# as14120_ddr.net
KiCad netlist of a schematic drawn in Altium Designer
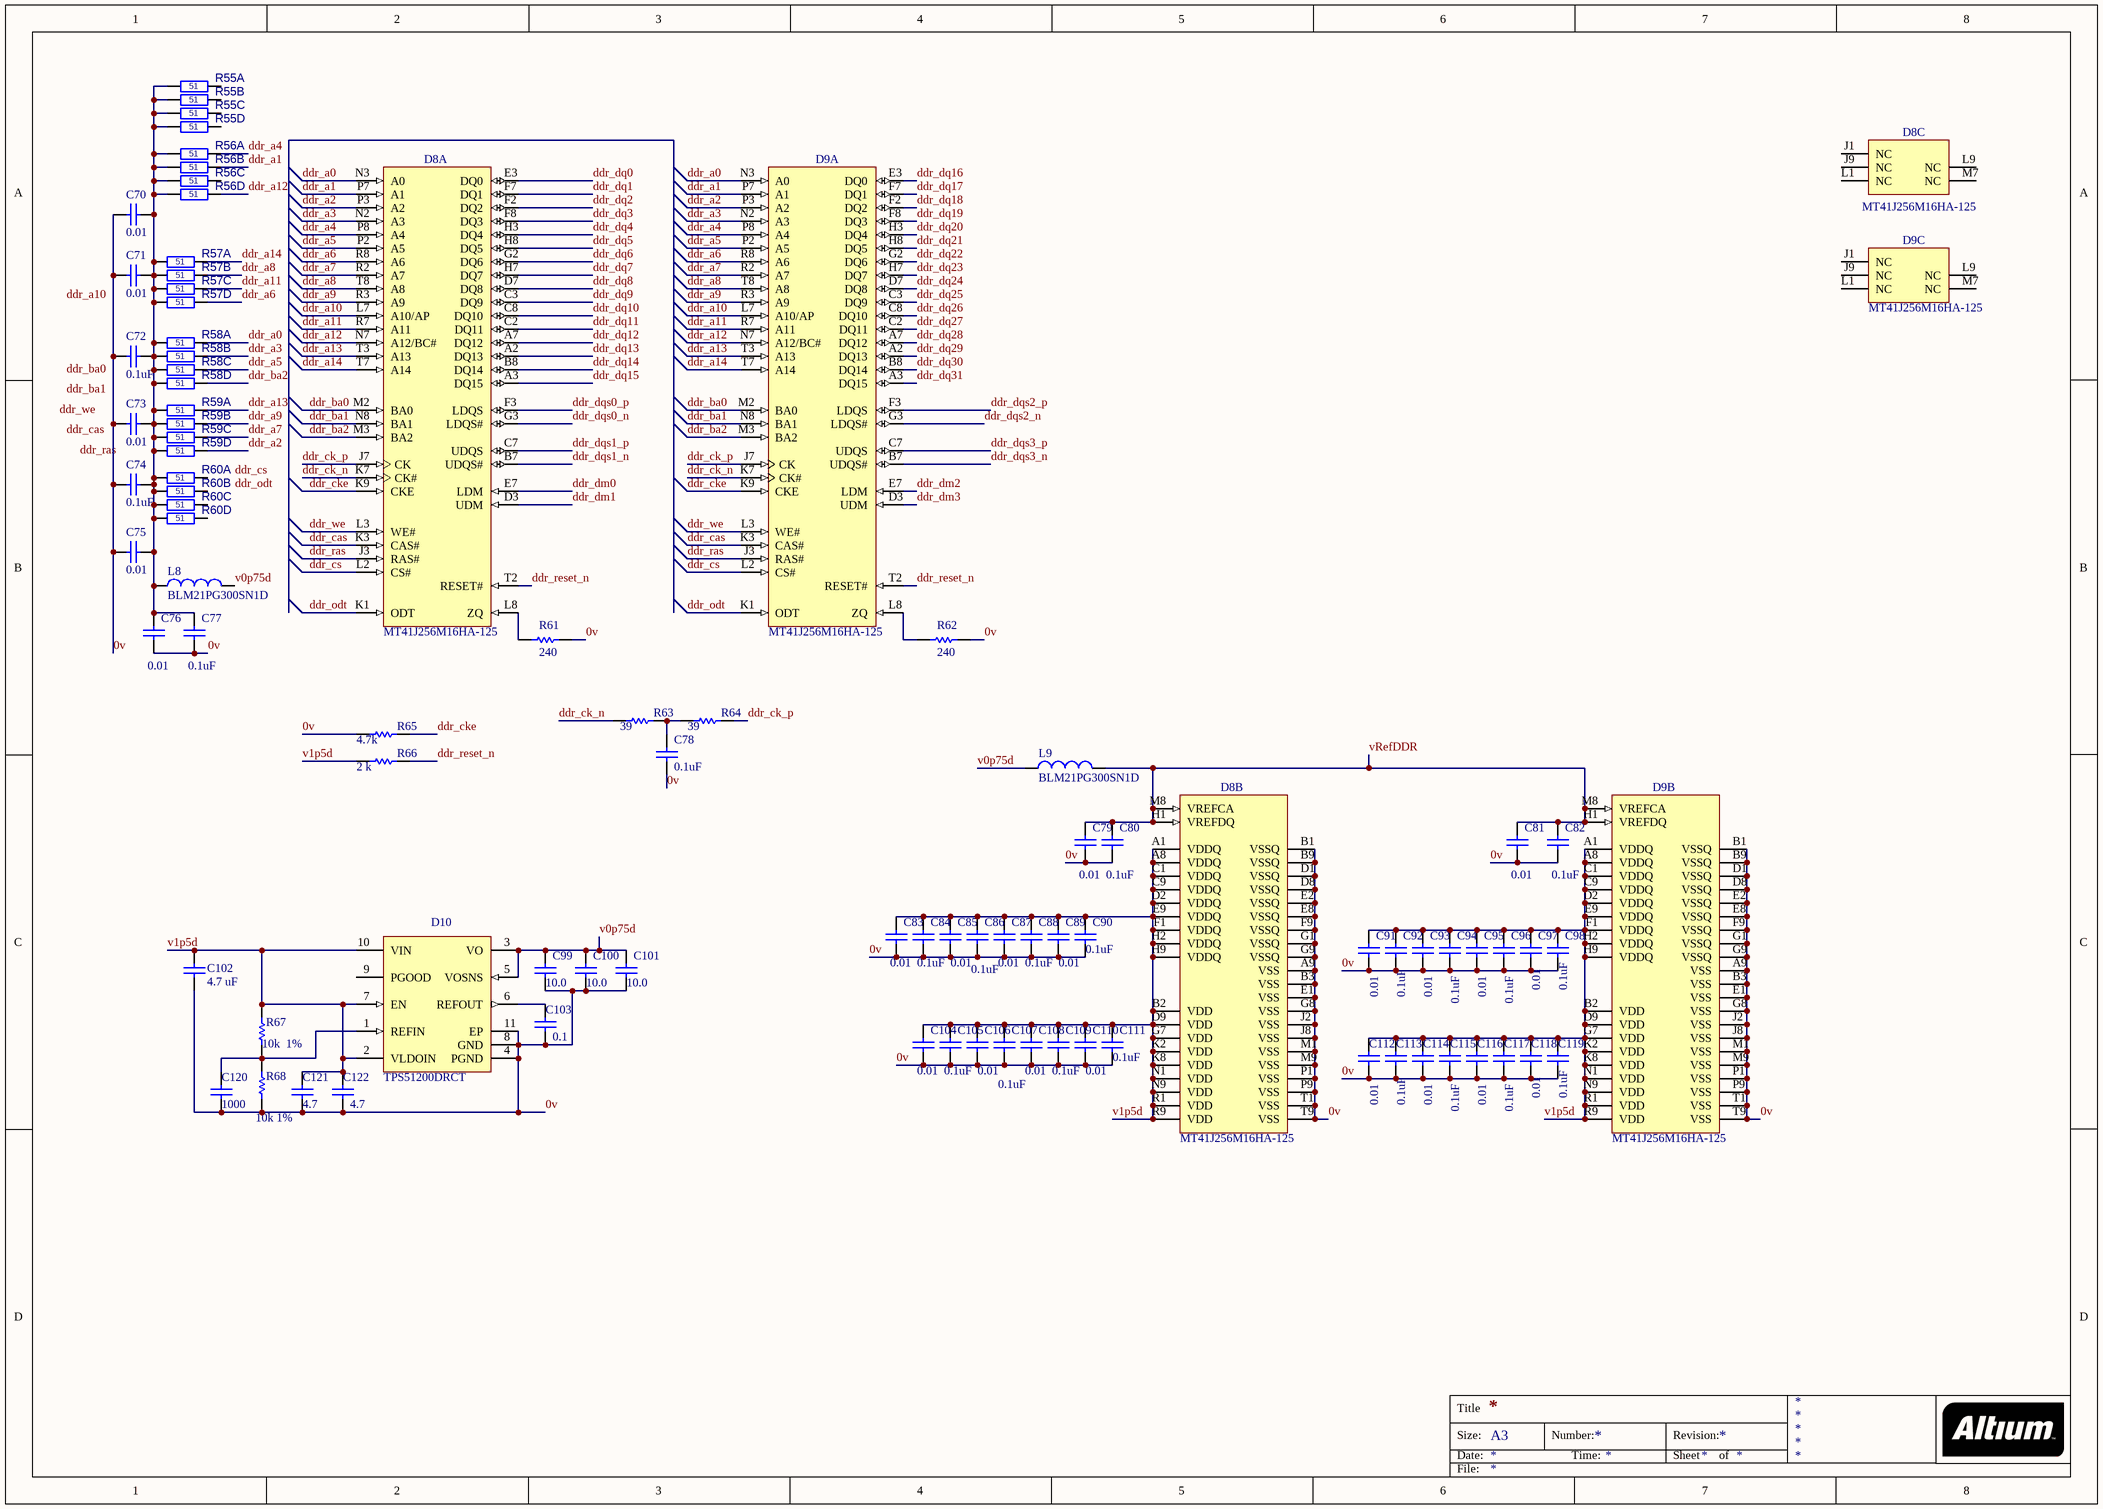
[diagram p0: as14120_ddr.SchDoc]

(export (version "E")
  (design (tool "Eeschema 10.0.6"))
  (components
    (comp (ref "C70")
      (value "0.01")
      (footprint "CAPC0402(1005)60_M")
      (description "CAP 1uF 10V ±20% 0402 (1005 Metric) Thickness 0.6mm SMD")
      (fields (field (name "TOLERANCE") "±20%") (field (name "Comment") "CAP 1uF 10V 0402(1005)"))
      (libsource (lib "as14120") (part "CAP_0402"))
    )
    (comp (ref "C71")
      (value "0.01")
      (footprint "CAPC0402(1005)60_M")
      (description "CAP 1uF 10V ±20% 0402 (1005 Metric) Thickness 0.6mm SMD")
      (fields (field (name "TOLERANCE") "±20%") (field (name "Comment") "CAP 1uF 10V 0402(1005)"))
      (libsource (lib "as14120") (part "CAP_0402"))
    )
    (comp (ref "C72")
      (value "0.1uF")
      (footprint "CAPC0402(1005)60_M")
      (description "CAP 1uF 10V ±20% 0402 (1005 Metric) Thickness 0.6mm SMD")
      (fields (field (name "TOLERANCE") "±20%") (field (name "Comment") "CAP 1uF 10V 0402(1005)"))
      (libsource (lib "as14120") (part "CAP_0402"))
    )
    (comp (ref "C73")
      (value "0.01")
      (footprint "CAPC0402(1005)60_M")
      (description "CAP 1uF 10V ±20% 0402 (1005 Metric) Thickness 0.6mm SMD")
      (fields (field (name "TOLERANCE") "±20%") (field (name "Comment") "CAP 1uF 10V 0402(1005)"))
      (libsource (lib "as14120") (part "CAP_0402"))
    )
    (comp (ref "C74")
      (value "0.1uF")
      (footprint "CAPC0402(1005)60_M")
      (description "CAP 1uF 10V ±20% 0402 (1005 Metric) Thickness 0.6mm SMD")
      (fields (field (name "TOLERANCE") "±20%") (field (name "Comment") "CAP 1uF 10V 0402(1005)"))
      (libsource (lib "as14120") (part "CAP_0402"))
    )
    (comp (ref "C75")
      (value "0.01")
      (footprint "CAPC0402(1005)60_M")
      (description "CAP 1uF 10V ±20% 0402 (1005 Metric) Thickness 0.6mm SMD")
      (fields (field (name "TOLERANCE") "±20%") (field (name "Comment") "CAP 1uF 10V 0402(1005)"))
      (libsource (lib "as14120") (part "CAP_0402"))
    )
    (comp (ref "C76")
      (value "0.01")
      (footprint "CAPC0402(1005)60_M")
      (description "CAP 1uF 10V ±20% 0402 (1005 Metric) Thickness 0.6mm SMD")
      (fields (field (name "TOLERANCE") "±20%") (field (name "Comment") "CAP 1uF 10V 0402(1005)"))
      (libsource (lib "as14120") (part "CAP_0402"))
    )
    (comp (ref "C77")
      (value "0.1uF")
      (footprint "CAPC0402(1005)60_M")
      (description "CAP 1uF 10V ±20% 0402 (1005 Metric) Thickness 0.6mm SMD")
      (fields (field (name "TOLERANCE") "±20%") (field (name "Comment") "CAP 1uF 10V 0402(1005)"))
      (libsource (lib "as14120") (part "CAP_0402"))
    )
    (comp (ref "C78")
      (value "0.1uF")
      (footprint "CAPC0402(1005)60_M")
      (description "CAP 1uF 10V ±20% 0402 (1005 Metric) Thickness 0.6mm SMD")
      (fields (field (name "TOLERANCE") "±20%") (field (name "Comment") "CAP 1uF 10V 0402(1005)"))
      (libsource (lib "as14120") (part "CAP_0402"))
    )
    (comp (ref "C79")
      (value "0.01")
      (footprint "CAPC0402(1005)60_M")
      (description "CAP 1uF 10V ±20% 0402 (1005 Metric) Thickness 0.6mm SMD")
      (fields (field (name "TOLERANCE") "±20%") (field (name "Comment") "CAP 1uF 10V 0402(1005)"))
      (libsource (lib "as14120") (part "CAP_0402"))
    )
    (comp (ref "C80")
      (value "0.1uF")
      (footprint "CAPC0402(1005)60_M")
      (description "CAP 1uF 10V ±20% 0402 (1005 Metric) Thickness 0.6mm SMD")
      (fields (field (name "TOLERANCE") "±20%") (field (name "Comment") "CAP 1uF 10V 0402(1005)"))
      (libsource (lib "as14120") (part "CAP_0402"))
    )
    (comp (ref "C81")
      (value "0.01")
      (footprint "CAPC0402(1005)60_M")
      (description "CAP 1uF 10V ±20% 0402 (1005 Metric) Thickness 0.6mm SMD")
      (fields (field (name "TOLERANCE") "±20%") (field (name "Comment") "CAP 1uF 10V 0402(1005)"))
      (libsource (lib "as14120") (part "CAP_0402"))
    )
    (comp (ref "C82")
      (value "0.1uF")
      (footprint "CAPC0402(1005)60_M")
      (description "CAP 1uF 10V ±20% 0402 (1005 Metric) Thickness 0.6mm SMD")
      (fields (field (name "TOLERANCE") "±20%") (field (name "Comment") "CAP 1uF 10V 0402(1005)"))
      (libsource (lib "as14120") (part "CAP_0402"))
    )
    (comp (ref "C83")
      (value "0.01")
      (footprint "CAPC0402(1005)60_M")
      (description "CAP 1uF 10V ±20% 0402 (1005 Metric) Thickness 0.6mm SMD")
      (fields (field (name "TOLERANCE") "±20%") (field (name "Comment") "CAP 1uF 10V 0402(1005)"))
      (libsource (lib "as14120") (part "CAP_0402"))
    )
    (comp (ref "C84")
      (value "0.1uF")
      (footprint "CAPC0402(1005)60_M")
      (description "CAP 1uF 10V ±20% 0402 (1005 Metric) Thickness 0.6mm SMD")
      (fields (field (name "TOLERANCE") "±20%") (field (name "Comment") "CAP 1uF 10V 0402(1005)"))
      (libsource (lib "as14120") (part "CAP_0402"))
    )
    (comp (ref "C85")
      (value "0.01")
      (footprint "CAPC0402(1005)60_M")
      (description "CAP 1uF 10V ±20% 0402 (1005 Metric) Thickness 0.6mm SMD")
      (fields (field (name "TOLERANCE") "±20%") (field (name "Comment") "CAP 1uF 10V 0402(1005)"))
      (libsource (lib "as14120") (part "CAP_0402"))
    )
    (comp (ref "C86")
      (value "0.1uF")
      (footprint "CAPC0402(1005)60_M")
      (description "CAP 1uF 10V ±20% 0402 (1005 Metric) Thickness 0.6mm SMD")
      (fields (field (name "TOLERANCE") "±20%") (field (name "Comment") "CAP 1uF 10V 0402(1005)"))
      (libsource (lib "as14120") (part "CAP_0402"))
    )
    (comp (ref "C87")
      (value "0.01")
      (footprint "CAPC0402(1005)60_M")
      (description "CAP 1uF 10V ±20% 0402 (1005 Metric) Thickness 0.6mm SMD")
      (fields (field (name "TOLERANCE") "±20%") (field (name "Comment") "CAP 1uF 10V 0402(1005)"))
      (libsource (lib "as14120") (part "CAP_0402"))
    )
    (comp (ref "C88")
      (value "0.1uF")
      (footprint "CAPC0402(1005)60_M")
      (description "CAP 1uF 10V ±20% 0402 (1005 Metric) Thickness 0.6mm SMD")
      (fields (field (name "TOLERANCE") "±20%") (field (name "Comment") "CAP 1uF 10V 0402(1005)"))
      (libsource (lib "as14120") (part "CAP_0402"))
    )
    (comp (ref "C89")
      (value "0.01")
      (footprint "CAPC0402(1005)60_M")
      (description "CAP 1uF 10V ±20% 0402 (1005 Metric) Thickness 0.6mm SMD")
      (fields (field (name "TOLERANCE") "±20%") (field (name "Comment") "CAP 1uF 10V 0402(1005)"))
      (libsource (lib "as14120") (part "CAP_0402"))
    )
    (comp (ref "C90")
      (value "0.1uF")
      (footprint "CAPC0402(1005)60_M")
      (description "CAP 1uF 10V ±20% 0402 (1005 Metric) Thickness 0.6mm SMD")
      (fields (field (name "TOLERANCE") "±20%") (field (name "Comment") "CAP 1uF 10V 0402(1005)"))
      (libsource (lib "as14120") (part "CAP_0402"))
    )
    (comp (ref "C91")
      (value "0.01")
      (footprint "CAPC0402(1005)60_M")
      (description "CAP 1uF 10V ±20% 0402 (1005 Metric) Thickness 0.6mm SMD")
      (fields (field (name "TOLERANCE") "±20%") (field (name "Comment") "CAP 1uF 10V 0402(1005)"))
      (libsource (lib "as14120") (part "CAP_0402"))
    )
    (comp (ref "C92")
      (value "0.1uF")
      (footprint "CAPC0402(1005)60_M")
      (description "CAP 1uF 10V ±20% 0402 (1005 Metric) Thickness 0.6mm SMD")
      (fields (field (name "TOLERANCE") "±20%") (field (name "Comment") "CAP 1uF 10V 0402(1005)"))
      (libsource (lib "as14120") (part "CAP_0402"))
    )
    (comp (ref "C93")
      (value "0.01")
      (footprint "CAPC0402(1005)60_M")
      (description "CAP 1uF 10V ±20% 0402 (1005 Metric) Thickness 0.6mm SMD")
      (fields (field (name "TOLERANCE") "±20%") (field (name "Comment") "CAP 1uF 10V 0402(1005)"))
      (libsource (lib "as14120") (part "CAP_0402"))
    )
    (comp (ref "C94")
      (value "0.1uF")
      (footprint "CAPC0402(1005)60_M")
      (description "CAP 1uF 10V ±20% 0402 (1005 Metric) Thickness 0.6mm SMD")
      (fields (field (name "TOLERANCE") "±20%") (field (name "Comment") "CAP 1uF 10V 0402(1005)"))
      (libsource (lib "as14120") (part "CAP_0402"))
    )
    (comp (ref "C95")
      (value "0.01")
      (footprint "CAPC0402(1005)60_M")
      (description "CAP 1uF 10V ±20% 0402 (1005 Metric) Thickness 0.6mm SMD")
      (fields (field (name "TOLERANCE") "±20%") (field (name "Comment") "CAP 1uF 10V 0402(1005)"))
      (libsource (lib "as14120") (part "CAP_0402"))
    )
    (comp (ref "C96")
      (value "0.1uF")
      (footprint "CAPC0402(1005)60_M")
      (description "CAP 1uF 10V ±20% 0402 (1005 Metric) Thickness 0.6mm SMD")
      (fields (field (name "TOLERANCE") "±20%") (field (name "Comment") "CAP 1uF 10V 0402(1005)"))
      (libsource (lib "as14120") (part "CAP_0402"))
    )
    (comp (ref "C97")
      (value "0.01")
      (footprint "CAPC0402(1005)60_M")
      (description "CAP 1uF 10V ±20% 0402 (1005 Metric) Thickness 0.6mm SMD")
      (fields (field (name "TOLERANCE") "±20%") (field (name "Comment") "CAP 1uF 10V 0402(1005)"))
      (libsource (lib "as14120") (part "CAP_0402"))
    )
    (comp (ref "C98")
      (value "0.1uF")
      (footprint "CAPC0402(1005)60_M")
      (description "CAP 1uF 10V ±20% 0402 (1005 Metric) Thickness 0.6mm SMD")
      (fields (field (name "TOLERANCE") "±20%") (field (name "Comment") "CAP 1uF 10V 0402(1005)"))
      (libsource (lib "as14120") (part "CAP_0402"))
    )
    (comp (ref "C99")
      (value "10.0")
      (footprint "CAPC0805(2012)100_N")
      (fields (field (name "Comment") "CAP_0805"))
      (libsource (lib "as14120") (part "CAP_0805"))
    )
    (comp (ref "C100")
      (value "10.0")
      (footprint "CAPC0805(2012)100_N")
      (fields (field (name "Comment") "CAP_0805"))
      (libsource (lib "as14120") (part "CAP_0805"))
    )
    (comp (ref "C101")
      (value "10.0")
      (footprint "CAPC0805(2012)100_N")
      (fields (field (name "Comment") "CAP_0805"))
      (libsource (lib "as14120") (part "CAP_0805"))
    )
    (comp (ref "C102")
      (value "4.7 uF")
      (footprint "CAPC0805(2012)100_N")
      (fields (field (name "Comment") "CAP_0805"))
      (libsource (lib "as14120") (part "CAP_0805"))
    )
    (comp (ref "C103")
      (value "0.1")
      (footprint "CAPC0805(2012)100_N")
      (fields (field (name "Comment") "CAP_0805"))
      (libsource (lib "as14120") (part "CAP_0805"))
    )
    (comp (ref "C104")
      (value "0.01")
      (footprint "CAPC0402(1005)60_M")
      (description "CAP 1uF 10V ±20% 0402 (1005 Metric) Thickness 0.6mm SMD")
      (fields (field (name "TOLERANCE") "±20%") (field (name "Comment") "CAP 1uF 10V 0402(1005)"))
      (libsource (lib "as14120") (part "CAP_0402"))
    )
    (comp (ref "C105")
      (value "0.1uF")
      (footprint "CAPC0402(1005)60_M")
      (description "CAP 1uF 10V ±20% 0402 (1005 Metric) Thickness 0.6mm SMD")
      (fields (field (name "TOLERANCE") "±20%") (field (name "Comment") "CAP 1uF 10V 0402(1005)"))
      (libsource (lib "as14120") (part "CAP_0402"))
    )
    (comp (ref "C106")
      (value "0.01")
      (footprint "CAPC0402(1005)60_M")
      (description "CAP 1uF 10V ±20% 0402 (1005 Metric) Thickness 0.6mm SMD")
      (fields (field (name "TOLERANCE") "±20%") (field (name "Comment") "CAP 1uF 10V 0402(1005)"))
      (libsource (lib "as14120") (part "CAP_0402"))
    )
    (comp (ref "C107")
      (value "0.1uF")
      (footprint "CAPC0402(1005)60_M")
      (description "CAP 1uF 10V ±20% 0402 (1005 Metric) Thickness 0.6mm SMD")
      (fields (field (name "TOLERANCE") "±20%") (field (name "Comment") "CAP 1uF 10V 0402(1005)"))
      (libsource (lib "as14120") (part "CAP_0402"))
    )
    (comp (ref "C108")
      (value "0.01")
      (footprint "CAPC0402(1005)60_M")
      (description "CAP 1uF 10V ±20% 0402 (1005 Metric) Thickness 0.6mm SMD")
      (fields (field (name "TOLERANCE") "±20%") (field (name "Comment") "CAP 1uF 10V 0402(1005)"))
      (libsource (lib "as14120") (part "CAP_0402"))
    )
    (comp (ref "C109")
      (value "0.1uF")
      (footprint "CAPC0402(1005)60_M")
      (description "CAP 1uF 10V ±20% 0402 (1005 Metric) Thickness 0.6mm SMD")
      (fields (field (name "TOLERANCE") "±20%") (field (name "Comment") "CAP 1uF 10V 0402(1005)"))
      (libsource (lib "as14120") (part "CAP_0402"))
    )
    (comp (ref "C110")
      (value "0.01")
      (footprint "CAPC0402(1005)60_M")
      (description "CAP 1uF 10V ±20% 0402 (1005 Metric) Thickness 0.6mm SMD")
      (fields (field (name "TOLERANCE") "±20%") (field (name "Comment") "CAP 1uF 10V 0402(1005)"))
      (libsource (lib "as14120") (part "CAP_0402"))
    )
    (comp (ref "C111")
      (value "0.1uF")
      (footprint "CAPC0402(1005)60_M")
      (description "CAP 1uF 10V ±20% 0402 (1005 Metric) Thickness 0.6mm SMD")
      (fields (field (name "TOLERANCE") "±20%") (field (name "Comment") "CAP 1uF 10V 0402(1005)"))
      (libsource (lib "as14120") (part "CAP_0402"))
    )
    (comp (ref "C112")
      (value "0.01")
      (footprint "CAPC0402(1005)60_M")
      (description "CAP 1uF 10V ±20% 0402 (1005 Metric) Thickness 0.6mm SMD")
      (fields (field (name "TOLERANCE") "±20%") (field (name "Comment") "CAP 1uF 10V 0402(1005)"))
      (libsource (lib "as14120") (part "CAP_0402"))
    )
    (comp (ref "C113")
      (value "0.1uF")
      (footprint "CAPC0402(1005)60_M")
      (description "CAP 1uF 10V ±20% 0402 (1005 Metric) Thickness 0.6mm SMD")
      (fields (field (name "TOLERANCE") "±20%") (field (name "Comment") "CAP 1uF 10V 0402(1005)"))
      (libsource (lib "as14120") (part "CAP_0402"))
    )
    (comp (ref "C114")
      (value "0.01")
      (footprint "CAPC0402(1005)60_M")
      (description "CAP 1uF 10V ±20% 0402 (1005 Metric) Thickness 0.6mm SMD")
      (fields (field (name "TOLERANCE") "±20%") (field (name "Comment") "CAP 1uF 10V 0402(1005)"))
      (libsource (lib "as14120") (part "CAP_0402"))
    )
    (comp (ref "C115")
      (value "0.1uF")
      (footprint "CAPC0402(1005)60_M")
      (description "CAP 1uF 10V ±20% 0402 (1005 Metric) Thickness 0.6mm SMD")
      (fields (field (name "TOLERANCE") "±20%") (field (name "Comment") "CAP 1uF 10V 0402(1005)"))
      (libsource (lib "as14120") (part "CAP_0402"))
    )
    (comp (ref "C116")
      (value "0.01")
      (footprint "CAPC0402(1005)60_M")
      (description "CAP 1uF 10V ±20% 0402 (1005 Metric) Thickness 0.6mm SMD")
      (fields (field (name "TOLERANCE") "±20%") (field (name "Comment") "CAP 1uF 10V 0402(1005)"))
      (libsource (lib "as14120") (part "CAP_0402"))
    )
    (comp (ref "C117")
      (value "0.1uF")
      (footprint "CAPC0402(1005)60_M")
      (description "CAP 1uF 10V ±20% 0402 (1005 Metric) Thickness 0.6mm SMD")
      (fields (field (name "TOLERANCE") "±20%") (field (name "Comment") "CAP 1uF 10V 0402(1005)"))
      (libsource (lib "as14120") (part "CAP_0402"))
    )
    (comp (ref "C118")
      (value "0.01")
      (footprint "CAPC0402(1005)60_M")
      (description "CAP 1uF 10V ±20% 0402 (1005 Metric) Thickness 0.6mm SMD")
      (fields (field (name "TOLERANCE") "±20%") (field (name "Comment") "CAP 1uF 10V 0402(1005)"))
      (libsource (lib "as14120") (part "CAP_0402"))
    )
    (comp (ref "C119")
      (value "0.1uF")
      (footprint "CAPC0402(1005)60_M")
      (description "CAP 1uF 10V ±20% 0402 (1005 Metric) Thickness 0.6mm SMD")
      (fields (field (name "TOLERANCE") "±20%") (field (name "Comment") "CAP 1uF 10V 0402(1005)"))
      (libsource (lib "as14120") (part "CAP_0402"))
    )
    (comp (ref "C120")
      (value "1000")
      (footprint "CAPC0805(2012)100_N")
      (fields (field (name "Comment") "CAP_0805"))
      (libsource (lib "as14120") (part "CAP_0805"))
    )
    (comp (ref "C121")
      (value "4.7")
      (footprint "CAPC0805(2012)100_N")
      (fields (field (name "Comment") "CAP_0805"))
      (libsource (lib "as14120") (part "CAP_0805"))
    )
    (comp (ref "C122")
      (value "4.7")
      (footprint "CAPC0805(2012)100_N")
      (fields (field (name "Comment") "CAP_0805"))
      (libsource (lib "as14120") (part "CAP_0805"))
    )
    (comp (ref "D8")
      (value "MT41J256M16HA-125")
      (footprint "MICT-HA-96")
      (description "4Gb DDR3-1600 SDRAM, 256Mb x 16, 1.25ns, 1.5V, 0 to 95 degC, 96-Ball FBGA, Pb-Free")
      (fields (field (name "VOLTAGE") "1.5V ") (field (name "MANUFACTURER") "Micron"))
      (libsource (lib "Micron Memory DDR3 SDRAM") (part "MT41J256M16HA-125"))
    )
    (comp (ref "D9")
      (value "MT41J256M16HA-125")
      (footprint "MICT-HA-96")
      (description "4Gb DDR3-1600 SDRAM, 256Mb x 16, 1.25ns, 1.5V, 0 to 95 degC, 96-Ball FBGA, Pb-Free")
      (fields (field (name "VOLTAGE") "1.5V ") (field (name "MANUFACTURER") "Micron"))
      (libsource (lib "Micron Memory DDR3 SDRAM") (part "MT41J256M16HA-125"))
    )
    (comp (ref "D10")
      (value "TPS51200DRCT")
      (footprint "TI-DRC10-2400X1650TP_V")
      (fields (field (name "MANUFACTURER") "Texas Instruments"))
      (libsource (lib "TI Power Management Linear Regulator Single Channel LDO (400-7500mA)") (part "TPS51200DRCT"))
    )
    (comp (ref "L8")
      (value "BLM21PG300SN1D")
      (footprint "CAPC0805(2012)100_N")
      (libsource (lib "as14120") (part "Ferrite_beat"))
    )
    (comp (ref "L9")
      (value "BLM21PG300SN1D")
      (footprint "CAPC0805(2012)100_N")
      (libsource (lib "as14120") (part "Ferrite_beat"))
    )
    (comp (ref "R55")
      (value "51")
      (footprint "CAY16")
      (description "RES_CAY16")
      (libsource (lib "alexsb") (part "RES_CAY16"))
    )
    (comp (ref "R56")
      (value "51")
      (footprint "CAY16")
      (description "RES_CAY16")
      (libsource (lib "") (part "RES_CAY16_2"))
    )
    (comp (ref "R57")
      (value "51")
      (footprint "CAY16")
      (description "RES_CAY16")
      (libsource (lib "") (part "RES_CAY16_5"))
    )
    (comp (ref "R58")
      (value "51")
      (footprint "CAY16")
      (description "RES_CAY16")
      (libsource (lib "") (part "RES_CAY16_2"))
    )
    (comp (ref "R59")
      (value "51")
      (footprint "CAY16")
      (description "RES_CAY16")
      (libsource (lib "alexsb") (part "RES_CAY16"))
    )
    (comp (ref "R60")
      (value "51")
      (footprint "CAY16")
      (description "RES_CAY16")
      (libsource (lib "alexsb") (part "RES_CAY16"))
    )
    (comp (ref "R61")
      (value "240")
      (footprint "RESC0805(2012)_L")
      (description "1K 0.125W 1% 0805 (2012 Metric)  SMD")
      (fields (field (name "TOLERANCE") "1 %") (field (name "POWER") "0.125 W"))
      (libsource (lib "as14120") (part "RES_0805"))
    )
    (comp (ref "R62")
      (value "240")
      (footprint "RESC0805(2012)_L")
      (description "1K 0.125W 1% 0805 (2012 Metric)  SMD")
      (fields (field (name "TOLERANCE") "1 %") (field (name "POWER") "0.125 W"))
      (libsource (lib "as14120") (part "RES_0805"))
    )
    (comp (ref "R63")
      (value "39")
      (footprint "RESC0805(2012)_L")
      (description "1K 0.125W 1% 0805 (2012 Metric)  SMD")
      (fields (field (name "TOLERANCE") "1 %") (field (name "POWER") "0.125 W"))
      (libsource (lib "as14120") (part "RES_0805"))
    )
    (comp (ref "R64")
      (value "39")
      (footprint "RESC0805(2012)_L")
      (description "1K 0.125W 1% 0805 (2012 Metric)  SMD")
      (fields (field (name "TOLERANCE") "1 %") (field (name "POWER") "0.125 W"))
      (libsource (lib "as14120") (part "RES_0805"))
    )
    (comp (ref "R65")
      (value "4.7k")
      (footprint "RESC0805(2012)_L")
      (description "1K 0.125W 1% 0805 (2012 Metric)  SMD")
      (fields (field (name "TOLERANCE") "1 %") (field (name "POWER") "0.125 W"))
      (libsource (lib "as14120") (part "RES_0805"))
    )
    (comp (ref "R66")
      (value "2 k")
      (footprint "RESC0805(2012)_L")
      (description "1K 0.125W 1% 0805 (2012 Metric)  SMD")
      (fields (field (name "TOLERANCE") "1 %") (field (name "POWER") "0.125 W"))
      (libsource (lib "as14120") (part "RES_0805"))
    )
    (comp (ref "R67")
      (value "10k  1%")
      (footprint "RESC0805(2012)_L")
      (description "1K 0.125W 1% 0805 (2012 Metric)  SMD")
      (fields (field (name "TOLERANCE") "1 %") (field (name "POWER") "0.125 W"))
      (libsource (lib "as14120") (part "RES_0805"))
    )
    (comp (ref "R68")
      (value "10k 1%")
      (footprint "RESC0805(2012)_L")
      (description "1K 0.125W 1% 0805 (2012 Metric)  SMD")
      (fields (field (name "TOLERANCE") "1 %") (field (name "POWER") "0.125 W"))
      (libsource (lib "as14120") (part "RES_0805"))
    )
  )
  (nets
    (net (code "1") (name "/0v") (class "Default")
      (node (ref "C100") (pin "1") (pinfunction "1_1") (pintype "passive"))
      (node (ref "C101") (pin "1") (pinfunction "1_1") (pintype "passive"))
      (node (ref "C102") (pin "1") (pinfunction "1_1") (pintype "passive"))
      (node (ref "C103") (pin "1") (pinfunction "1_1") (pintype "passive"))
      (node (ref "C104") (pin "1") (pinfunction "1_1") (pintype "passive"))
      (node (ref "C105") (pin "1") (pinfunction "1_1") (pintype "passive"))
      (node (ref "C106") (pin "1") (pinfunction "1_1") (pintype "passive"))
      (node (ref "C107") (pin "1") (pinfunction "1_1") (pintype "passive"))
      (node (ref "C108") (pin "1") (pinfunction "1_1") (pintype "passive"))
      (node (ref "C109") (pin "1") (pinfunction "1_1") (pintype "passive"))
      (node (ref "C110") (pin "1") (pinfunction "1_1") (pintype "passive"))
      (node (ref "C111") (pin "1") (pinfunction "1_1") (pintype "passive"))
      (node (ref "C112") (pin "1") (pinfunction "1_1") (pintype "passive"))
      (node (ref "C113") (pin "1") (pinfunction "1_1") (pintype "passive"))
      (node (ref "C114") (pin "1") (pinfunction "1_1") (pintype "passive"))
      (node (ref "C115") (pin "1") (pinfunction "1_1") (pintype "passive"))
      (node (ref "C116") (pin "1") (pinfunction "1_1") (pintype "passive"))
      (node (ref "C117") (pin "1") (pinfunction "1_1") (pintype "passive"))
      (node (ref "C118") (pin "1") (pinfunction "1_1") (pintype "passive"))
      (node (ref "C119") (pin "1") (pinfunction "1_1") (pintype "passive"))
      (node (ref "C120") (pin "1") (pinfunction "1_1") (pintype "passive"))
      (node (ref "C121") (pin "1") (pinfunction "1_1") (pintype "passive"))
      (node (ref "C122") (pin "1") (pinfunction "1_1") (pintype "passive"))
      (node (ref "C70") (pin "2") (pinfunction "2_2") (pintype "passive"))
      (node (ref "C71") (pin "2") (pinfunction "2_2") (pintype "passive"))
      (node (ref "C72") (pin "2") (pinfunction "2_2") (pintype "passive"))
      (node (ref "C73") (pin "2") (pinfunction "2_2") (pintype "passive"))
      (node (ref "C74") (pin "2") (pinfunction "2_2") (pintype "passive"))
      (node (ref "C75") (pin "2") (pinfunction "2_2") (pintype "passive"))
      (node (ref "C76") (pin "1") (pinfunction "1_1") (pintype "passive"))
      (node (ref "C77") (pin "1") (pinfunction "1_1") (pintype "passive"))
      (node (ref "C78") (pin "1") (pinfunction "1_1") (pintype "passive"))
      (node (ref "C79") (pin "1") (pinfunction "1_1") (pintype "passive"))
      (node (ref "C80") (pin "1") (pinfunction "1_1") (pintype "passive"))
      (node (ref "C81") (pin "1") (pinfunction "1_1") (pintype "passive"))
      (node (ref "C82") (pin "1") (pinfunction "1_1") (pintype "passive"))
      (node (ref "C83") (pin "1") (pinfunction "1_1") (pintype "passive"))
      (node (ref "C84") (pin "1") (pinfunction "1_1") (pintype "passive"))
      (node (ref "C85") (pin "1") (pinfunction "1_1") (pintype "passive"))
      (node (ref "C86") (pin "1") (pinfunction "1_1") (pintype "passive"))
      (node (ref "C87") (pin "1") (pinfunction "1_1") (pintype "passive"))
      (node (ref "C88") (pin "1") (pinfunction "1_1") (pintype "passive"))
      (node (ref "C89") (pin "1") (pinfunction "1_1") (pintype "passive"))
      (node (ref "C90") (pin "1") (pinfunction "1_1") (pintype "passive"))
      (node (ref "C91") (pin "1") (pinfunction "1_1") (pintype "passive"))
      (node (ref "C92") (pin "1") (pinfunction "1_1") (pintype "passive"))
      (node (ref "C93") (pin "1") (pinfunction "1_1") (pintype "passive"))
      (node (ref "C94") (pin "1") (pinfunction "1_1") (pintype "passive"))
      (node (ref "C95") (pin "1") (pinfunction "1_1") (pintype "passive"))
      (node (ref "C96") (pin "1") (pinfunction "1_1") (pintype "passive"))
      (node (ref "C97") (pin "1") (pinfunction "1_1") (pintype "passive"))
      (node (ref "C98") (pin "1") (pinfunction "1_1") (pintype "passive"))
      (node (ref "C99") (pin "1") (pinfunction "1_1") (pintype "passive"))
      (node (ref "D10") (pin "11") (pinfunction "EP_11") (pintype "power_in"))
      (node (ref "D10") (pin "4") (pinfunction "PGND_4") (pintype "power_in"))
      (node (ref "D10") (pin "8") (pinfunction "GND_8") (pintype "power_in"))
      (node (ref "D8") (pin "A9") (pinfunction "VSS_A9") (pintype "power_in"))
      (node (ref "D8") (pin "B1") (pinfunction "VSSQ_B1") (pintype "power_in"))
      (node (ref "D8") (pin "B3") (pinfunction "VSS_B3") (pintype "power_in"))
      (node (ref "D8") (pin "B9") (pinfunction "VSSQ_B9") (pintype "power_in"))
      (node (ref "D8") (pin "D1") (pinfunction "VSSQ_D1") (pintype "power_in"))
      (node (ref "D8") (pin "D8") (pinfunction "VSSQ_D8") (pintype "power_in"))
      (node (ref "D8") (pin "E1") (pinfunction "VSS_E1") (pintype "power_in"))
      (node (ref "D8") (pin "E2") (pinfunction "VSSQ_E2") (pintype "power_in"))
      (node (ref "D8") (pin "E8") (pinfunction "VSSQ_E8") (pintype "power_in"))
      (node (ref "D8") (pin "F9") (pinfunction "VSSQ_F9") (pintype "power_in"))
      (node (ref "D8") (pin "G1") (pinfunction "VSSQ_G1") (pintype "power_in"))
      (node (ref "D8") (pin "G8") (pinfunction "VSS_G8") (pintype "power_in"))
      (node (ref "D8") (pin "G9") (pinfunction "VSSQ_G9") (pintype "power_in"))
      (node (ref "D8") (pin "J2") (pinfunction "VSS_J2") (pintype "power_in"))
      (node (ref "D8") (pin "J8") (pinfunction "VSS_J8") (pintype "power_in"))
      (node (ref "D8") (pin "M1") (pinfunction "VSS_M1") (pintype "power_in"))
      (node (ref "D8") (pin "M9") (pinfunction "VSS_M9") (pintype "power_in"))
      (node (ref "D8") (pin "P1") (pinfunction "VSS_P1") (pintype "power_in"))
      (node (ref "D8") (pin "P9") (pinfunction "VSS_P9") (pintype "power_in"))
      (node (ref "D8") (pin "T1") (pinfunction "VSS_T1") (pintype "power_in"))
      (node (ref "D8") (pin "T9") (pinfunction "VSS_T9") (pintype "power_in"))
      (node (ref "D9") (pin "A9") (pinfunction "VSS_A9") (pintype "power_in"))
      (node (ref "D9") (pin "B1") (pinfunction "VSSQ_B1") (pintype "power_in"))
      (node (ref "D9") (pin "B3") (pinfunction "VSS_B3") (pintype "power_in"))
      (node (ref "D9") (pin "B9") (pinfunction "VSSQ_B9") (pintype "power_in"))
      (node (ref "D9") (pin "D1") (pinfunction "VSSQ_D1") (pintype "power_in"))
      (node (ref "D9") (pin "D8") (pinfunction "VSSQ_D8") (pintype "power_in"))
      (node (ref "D9") (pin "E1") (pinfunction "VSS_E1") (pintype "power_in"))
      (node (ref "D9") (pin "E2") (pinfunction "VSSQ_E2") (pintype "power_in"))
      (node (ref "D9") (pin "E8") (pinfunction "VSSQ_E8") (pintype "power_in"))
      (node (ref "D9") (pin "F9") (pinfunction "VSSQ_F9") (pintype "power_in"))
      (node (ref "D9") (pin "G1") (pinfunction "VSSQ_G1") (pintype "power_in"))
      (node (ref "D9") (pin "G8") (pinfunction "VSS_G8") (pintype "power_in"))
      (node (ref "D9") (pin "G9") (pinfunction "VSSQ_G9") (pintype "power_in"))
      (node (ref "D9") (pin "J2") (pinfunction "VSS_J2") (pintype "power_in"))
      (node (ref "D9") (pin "J8") (pinfunction "VSS_J8") (pintype "power_in"))
      (node (ref "D9") (pin "M1") (pinfunction "VSS_M1") (pintype "power_in"))
      (node (ref "D9") (pin "M9") (pinfunction "VSS_M9") (pintype "power_in"))
      (node (ref "D9") (pin "P1") (pinfunction "VSS_P1") (pintype "power_in"))
      (node (ref "D9") (pin "P9") (pinfunction "VSS_P9") (pintype "power_in"))
      (node (ref "D9") (pin "T1") (pinfunction "VSS_T1") (pintype "power_in"))
      (node (ref "D9") (pin "T9") (pinfunction "VSS_T9") (pintype "power_in"))
      (node (ref "R61") (pin "2") (pinfunction "2_2") (pintype "passive"))
      (node (ref "R62") (pin "2") (pinfunction "2_2") (pintype "passive"))
      (node (ref "R65") (pin "1") (pinfunction "1_1") (pintype "passive"))
      (node (ref "R68") (pin "1") (pinfunction "1_1") (pintype "passive"))
    )
    (net (code "2") (name "/ddr_a0") (class "Default")
      (node (ref "D8") (pin "N3") (pinfunction "A0_N3") (pintype "input"))
      (node (ref "D9") (pin "N3") (pinfunction "A0_N3") (pintype "input"))
      (node (ref "R58") (pin "6") (pinfunction "2_6") (pintype "passive"))
    )
    (net (code "3") (name "/ddr_a1") (class "Default")
      (node (ref "D8") (pin "P7") (pinfunction "A1_P7") (pintype "input"))
      (node (ref "D9") (pin "P7") (pinfunction "A1_P7") (pintype "input"))
      (node (ref "R56") (pin "5") (pinfunction "2_5") (pintype "passive"))
    )
    (net (code "4") (name "/ddr_a2") (class "Default")
      (node (ref "D8") (pin "P3") (pinfunction "A2_P3") (pintype "input"))
      (node (ref "D9") (pin "P3") (pinfunction "A2_P3") (pintype "input"))
      (node (ref "R59") (pin "5") (pinfunction "2_5") (pintype "passive"))
    )
    (net (code "5") (name "/ddr_a3") (class "Default")
      (node (ref "D8") (pin "N2") (pinfunction "A3_N2") (pintype "input"))
      (node (ref "D9") (pin "N2") (pinfunction "A3_N2") (pintype "input"))
      (node (ref "R58") (pin "5") (pinfunction "2_5") (pintype "passive"))
    )
    (net (code "6") (name "/ddr_a4") (class "Default")
      (node (ref "D8") (pin "P8") (pinfunction "A4_P8") (pintype "input"))
      (node (ref "D9") (pin "P8") (pinfunction "A4_P8") (pintype "input"))
      (node (ref "R56") (pin "6") (pinfunction "2_6") (pintype "passive"))
    )
    (net (code "7") (name "/ddr_a5") (class "Default")
      (node (ref "D8") (pin "P2") (pinfunction "A5_P2") (pintype "input"))
      (node (ref "D9") (pin "P2") (pinfunction "A5_P2") (pintype "input"))
      (node (ref "R58") (pin "8") (pinfunction "2_8") (pintype "passive"))
    )
    (net (code "8") (name "/ddr_a6") (class "Default")
      (node (ref "D8") (pin "R8") (pinfunction "A6_R8") (pintype "input"))
      (node (ref "D9") (pin "R8") (pinfunction "A6_R8") (pintype "input"))
      (node (ref "R57") (pin "7") (pinfunction "2_7") (pintype "passive"))
    )
    (net (code "9") (name "/ddr_a7") (class "Default")
      (node (ref "D8") (pin "R2") (pinfunction "A7_R2") (pintype "input"))
      (node (ref "D9") (pin "R2") (pinfunction "A7_R2") (pintype "input"))
      (node (ref "R59") (pin "6") (pinfunction "2_6") (pintype "passive"))
    )
    (net (code "10") (name "/ddr_a8") (class "Default")
      (node (ref "D8") (pin "T8") (pinfunction "A8_T8") (pintype "input"))
      (node (ref "D9") (pin "T8") (pinfunction "A8_T8") (pintype "input"))
      (node (ref "R57") (pin "8") (pinfunction "2_8") (pintype "passive"))
    )
    (net (code "11") (name "/ddr_a9") (class "Default")
      (node (ref "D8") (pin "R3") (pinfunction "A9_R3") (pintype "input"))
      (node (ref "D9") (pin "R3") (pinfunction "A9_R3") (pintype "input"))
      (node (ref "R59") (pin "7") (pinfunction "2_7") (pintype "passive"))
    )
    (net (code "12") (name "/ddr_a10") (class "Default")
      (node (ref "D8") (pin "L7") (pinfunction "A10/AP_L7") (pintype "input"))
      (node (ref "D9") (pin "L7") (pinfunction "A10/AP_L7") (pintype "input"))
    )
    (net (code "13") (name "/ddr_a11") (class "Default")
      (node (ref "D8") (pin "R7") (pinfunction "A11_R7") (pintype "input"))
      (node (ref "D9") (pin "R7") (pinfunction "A11_R7") (pintype "input"))
      (node (ref "R57") (pin "5") (pinfunction "2_5") (pintype "passive"))
    )
    (net (code "14") (name "/ddr_a12") (class "Default")
      (node (ref "D8") (pin "N7") (pinfunction "A12/BC#_N7") (pintype "input"))
      (node (ref "D9") (pin "N7") (pinfunction "A12/BC#_N7") (pintype "input"))
      (node (ref "R56") (pin "7") (pinfunction "2_7") (pintype "passive"))
    )
    (net (code "15") (name "/ddr_a13") (class "Default")
      (node (ref "D8") (pin "T3") (pinfunction "A13_T3") (pintype "input"))
      (node (ref "D9") (pin "T3") (pinfunction "A13_T3") (pintype "input"))
      (node (ref "R59") (pin "8") (pinfunction "2_8") (pintype "passive"))
    )
    (net (code "16") (name "/ddr_a14") (class "Default")
      (node (ref "D8") (pin "T7") (pinfunction "A14_T7") (pintype "input"))
      (node (ref "D9") (pin "T7") (pinfunction "A14_T7") (pintype "input"))
      (node (ref "R57") (pin "6") (pinfunction "2_6") (pintype "passive"))
    )
    (net (code "17") (name "/ddr_ba0") (class "Default")
      (node (ref "D8") (pin "M2") (pinfunction "BA0_M2") (pintype "input"))
      (node (ref "D9") (pin "M2") (pinfunction "BA0_M2") (pintype "input"))
    )
    (net (code "18") (name "/ddr_ba1") (class "Default")
      (node (ref "D8") (pin "N8") (pinfunction "BA1_N8") (pintype "input"))
      (node (ref "D9") (pin "N8") (pinfunction "BA1_N8") (pintype "input"))
    )
    (net (code "19") (name "/ddr_ba2") (class "Default")
      (node (ref "D8") (pin "M3") (pinfunction "BA2_M3") (pintype "input"))
      (node (ref "D9") (pin "M3") (pinfunction "BA2_M3") (pintype "input"))
      (node (ref "R58") (pin "7") (pinfunction "2_7") (pintype "passive"))
    )
    (net (code "20") (name "/ddr_cas") (class "Default")
      (node (ref "D8") (pin "K3") (pinfunction "CAS#_K3") (pintype "input"))
      (node (ref "D9") (pin "K3") (pinfunction "CAS#_K3") (pintype "input"))
    )
    (net (code "21") (name "/ddr_ck_n") (class "Default")
      (node (ref "D8") (pin "K7") (pinfunction "CK#_K7") (pintype "input"))
      (node (ref "D9") (pin "K7") (pinfunction "CK#_K7") (pintype "input"))
      (node (ref "R63") (pin "1") (pinfunction "1_1") (pintype "passive"))
    )
    (net (code "22") (name "/ddr_ck_p") (class "Default")
      (node (ref "D8") (pin "J7") (pinfunction "CK_J7") (pintype "input"))
      (node (ref "D9") (pin "J7") (pinfunction "CK_J7") (pintype "input"))
      (node (ref "R64") (pin "2") (pinfunction "2_2") (pintype "passive"))
    )
    (net (code "23") (name "/ddr_cke") (class "Default")
      (node (ref "D8") (pin "K9") (pinfunction "CKE_K9") (pintype "input"))
      (node (ref "D9") (pin "K9") (pinfunction "CKE_K9") (pintype "input"))
      (node (ref "R65") (pin "2") (pinfunction "2_2") (pintype "passive"))
    )
    (net (code "24") (name "/ddr_cs") (class "Default")
      (node (ref "D8") (pin "L2") (pinfunction "CS#_L2") (pintype "input"))
      (node (ref "D9") (pin "L2") (pinfunction "CS#_L2") (pintype "input"))
    )
    (net (code "25") (name "/ddr_dm0") (class "Default")
      (node (ref "D8") (pin "E7") (pinfunction "LDM_E7") (pintype "input"))
    )
    (net (code "26") (name "/ddr_dm1") (class "Default")
      (node (ref "D8") (pin "D3") (pinfunction "UDM_D3") (pintype "input"))
    )
    (net (code "27") (name "/ddr_dm2") (class "Default")
      (node (ref "D9") (pin "E7") (pinfunction "LDM_E7") (pintype "input"))
    )
    (net (code "28") (name "/ddr_dm3") (class "Default")
      (node (ref "D9") (pin "D3") (pinfunction "UDM_D3") (pintype "input"))
    )
    (net (code "29") (name "/ddr_dq0") (class "Default")
      (node (ref "D8") (pin "E3") (pinfunction "DQ0_E3") (pintype "bidirectional"))
    )
    (net (code "30") (name "/ddr_dq1") (class "Default")
      (node (ref "D8") (pin "F7") (pinfunction "DQ1_F7") (pintype "bidirectional"))
    )
    (net (code "31") (name "/ddr_dq2") (class "Default")
      (node (ref "D8") (pin "F2") (pinfunction "DQ2_F2") (pintype "bidirectional"))
    )
    (net (code "32") (name "/ddr_dq3") (class "Default")
      (node (ref "D8") (pin "F8") (pinfunction "DQ3_F8") (pintype "bidirectional"))
    )
    (net (code "33") (name "/ddr_dq4") (class "Default")
      (node (ref "D8") (pin "H3") (pinfunction "DQ4_H3") (pintype "bidirectional"))
    )
    (net (code "34") (name "/ddr_dq5") (class "Default")
      (node (ref "D8") (pin "H8") (pinfunction "DQ5_H8") (pintype "bidirectional"))
    )
    (net (code "35") (name "/ddr_dq6") (class "Default")
      (node (ref "D8") (pin "G2") (pinfunction "DQ6_G2") (pintype "bidirectional"))
    )
    (net (code "36") (name "/ddr_dq7") (class "Default")
      (node (ref "D8") (pin "H7") (pinfunction "DQ7_H7") (pintype "bidirectional"))
    )
    (net (code "37") (name "/ddr_dq8") (class "Default")
      (node (ref "D8") (pin "D7") (pinfunction "DQ8_D7") (pintype "bidirectional"))
    )
    (net (code "38") (name "/ddr_dq9") (class "Default")
      (node (ref "D8") (pin "C3") (pinfunction "DQ9_C3") (pintype "bidirectional"))
    )
    (net (code "39") (name "/ddr_dq10") (class "Default")
      (node (ref "D8") (pin "C8") (pinfunction "DQ10_C8") (pintype "bidirectional"))
    )
    (net (code "40") (name "/ddr_dq11") (class "Default")
      (node (ref "D8") (pin "C2") (pinfunction "DQ11_C2") (pintype "bidirectional"))
    )
    (net (code "41") (name "/ddr_dq12") (class "Default")
      (node (ref "D8") (pin "A7") (pinfunction "DQ12_A7") (pintype "bidirectional"))
    )
    (net (code "42") (name "/ddr_dq13") (class "Default")
      (node (ref "D8") (pin "A2") (pinfunction "DQ13_A2") (pintype "bidirectional"))
    )
    (net (code "43") (name "/ddr_dq14") (class "Default")
      (node (ref "D8") (pin "B8") (pinfunction "DQ14_B8") (pintype "bidirectional"))
    )
    (net (code "44") (name "/ddr_dq15") (class "Default")
      (node (ref "D8") (pin "A3") (pinfunction "DQ15_A3") (pintype "bidirectional"))
    )
    (net (code "45") (name "/ddr_dq16") (class "Default")
      (node (ref "D9") (pin "E3") (pinfunction "DQ0_E3") (pintype "bidirectional"))
    )
    (net (code "46") (name "/ddr_dq17") (class "Default")
      (node (ref "D9") (pin "F7") (pinfunction "DQ1_F7") (pintype "bidirectional"))
    )
    (net (code "47") (name "/ddr_dq18") (class "Default")
      (node (ref "D9") (pin "F2") (pinfunction "DQ2_F2") (pintype "bidirectional"))
    )
    (net (code "48") (name "/ddr_dq19") (class "Default")
      (node (ref "D9") (pin "F8") (pinfunction "DQ3_F8") (pintype "bidirectional"))
    )
    (net (code "49") (name "/ddr_dq20") (class "Default")
      (node (ref "D9") (pin "H3") (pinfunction "DQ4_H3") (pintype "bidirectional"))
    )
    (net (code "50") (name "/ddr_dq21") (class "Default")
      (node (ref "D9") (pin "H8") (pinfunction "DQ5_H8") (pintype "bidirectional"))
    )
    (net (code "51") (name "/ddr_dq22") (class "Default")
      (node (ref "D9") (pin "G2") (pinfunction "DQ6_G2") (pintype "bidirectional"))
    )
    (net (code "52") (name "/ddr_dq23") (class "Default")
      (node (ref "D9") (pin "H7") (pinfunction "DQ7_H7") (pintype "bidirectional"))
    )
    (net (code "53") (name "/ddr_dq24") (class "Default")
      (node (ref "D9") (pin "D7") (pinfunction "DQ8_D7") (pintype "bidirectional"))
    )
    (net (code "54") (name "/ddr_dq25") (class "Default")
      (node (ref "D9") (pin "C3") (pinfunction "DQ9_C3") (pintype "bidirectional"))
    )
    (net (code "55") (name "/ddr_dq26") (class "Default")
      (node (ref "D9") (pin "C8") (pinfunction "DQ10_C8") (pintype "bidirectional"))
    )
    (net (code "56") (name "/ddr_dq27") (class "Default")
      (node (ref "D9") (pin "C2") (pinfunction "DQ11_C2") (pintype "bidirectional"))
    )
    (net (code "57") (name "/ddr_dq28") (class "Default")
      (node (ref "D9") (pin "A7") (pinfunction "DQ12_A7") (pintype "bidirectional"))
    )
    (net (code "58") (name "/ddr_dq29") (class "Default")
      (node (ref "D9") (pin "A2") (pinfunction "DQ13_A2") (pintype "bidirectional"))
    )
    (net (code "59") (name "/ddr_dq30") (class "Default")
      (node (ref "D9") (pin "B8") (pinfunction "DQ14_B8") (pintype "bidirectional"))
    )
    (net (code "60") (name "/ddr_dq31") (class "Default")
      (node (ref "D9") (pin "A3") (pinfunction "DQ15_A3") (pintype "bidirectional"))
    )
    (net (code "61") (name "/ddr_dqs0_n") (class "Default")
      (node (ref "D8") (pin "G3") (pinfunction "LDQS#_G3") (pintype "bidirectional"))
    )
    (net (code "62") (name "/ddr_dqs0_p") (class "Default")
      (node (ref "D8") (pin "F3") (pinfunction "LDQS_F3") (pintype "bidirectional"))
    )
    (net (code "63") (name "/ddr_dqs1_n") (class "Default")
      (node (ref "D8") (pin "B7") (pinfunction "UDQS#_B7") (pintype "bidirectional"))
    )
    (net (code "64") (name "/ddr_dqs1_p") (class "Default")
      (node (ref "D8") (pin "C7") (pinfunction "UDQS_C7") (pintype "bidirectional"))
    )
    (net (code "65") (name "/ddr_dqs2_n") (class "Default")
      (node (ref "D9") (pin "G3") (pinfunction "LDQS#_G3") (pintype "bidirectional"))
    )
    (net (code "66") (name "/ddr_dqs2_p") (class "Default")
      (node (ref "D9") (pin "F3") (pinfunction "LDQS_F3") (pintype "bidirectional"))
    )
    (net (code "67") (name "/ddr_dqs3_n") (class "Default")
      (node (ref "D9") (pin "B7") (pinfunction "UDQS#_B7") (pintype "bidirectional"))
    )
    (net (code "68") (name "/ddr_dqs3_p") (class "Default")
      (node (ref "D9") (pin "C7") (pinfunction "UDQS_C7") (pintype "bidirectional"))
    )
    (net (code "69") (name "/ddr_odt") (class "Default")
      (node (ref "D8") (pin "K1") (pinfunction "ODT_K1") (pintype "input"))
      (node (ref "D9") (pin "K1") (pinfunction "ODT_K1") (pintype "input"))
    )
    (net (code "70") (name "/ddr_ras") (class "Default")
      (node (ref "D8") (pin "J3") (pinfunction "RAS#_J3") (pintype "input"))
      (node (ref "D9") (pin "J3") (pinfunction "RAS#_J3") (pintype "input"))
    )
    (net (code "71") (name "/ddr_reset_n") (class "Default")
      (node (ref "D8") (pin "T2") (pinfunction "RESET#_T2") (pintype "input"))
      (node (ref "D9") (pin "T2") (pinfunction "RESET#_T2") (pintype "input"))
      (node (ref "R66") (pin "2") (pinfunction "2_2") (pintype "passive"))
    )
    (net (code "72") (name "/ddr_we") (class "Default")
      (node (ref "D8") (pin "L3") (pinfunction "WE#_L3") (pintype "input"))
      (node (ref "D9") (pin "L3") (pinfunction "WE#_L3") (pintype "input"))
    )
    (net (code "73") (name "/v0p75d") (class "Default")
      (node (ref "C100") (pin "2") (pinfunction "2_2") (pintype "passive"))
      (node (ref "C101") (pin "2") (pinfunction "2_2") (pintype "passive"))
      (node (ref "C99") (pin "2") (pinfunction "2_2") (pintype "passive"))
      (node (ref "D10") (pin "3") (pinfunction "VO_3") (pintype "power_in"))
      (node (ref "D10") (pin "5") (pinfunction "VOSNS_5") (pintype "input"))
      (node (ref "L8") (pin "2") (pinfunction "2_2") (pintype "passive"))
      (node (ref "L9") (pin "1") (pinfunction "1_1") (pintype "passive"))
    )
    (net (code "74") (name "/v1p5d") (class "Default")
      (node (ref "C102") (pin "2") (pinfunction "2_2") (pintype "passive"))
      (node (ref "C104") (pin "2") (pinfunction "2_2") (pintype "passive"))
      (node (ref "C105") (pin "2") (pinfunction "2_2") (pintype "passive"))
      (node (ref "C106") (pin "2") (pinfunction "2_2") (pintype "passive"))
      (node (ref "C107") (pin "2") (pinfunction "2_2") (pintype "passive"))
      (node (ref "C108") (pin "2") (pinfunction "2_2") (pintype "passive"))
      (node (ref "C109") (pin "2") (pinfunction "2_2") (pintype "passive"))
      (node (ref "C110") (pin "2") (pinfunction "2_2") (pintype "passive"))
      (node (ref "C111") (pin "2") (pinfunction "2_2") (pintype "passive"))
      (node (ref "C112") (pin "2") (pinfunction "2_2") (pintype "passive"))
      (node (ref "C113") (pin "2") (pinfunction "2_2") (pintype "passive"))
      (node (ref "C114") (pin "2") (pinfunction "2_2") (pintype "passive"))
      (node (ref "C115") (pin "2") (pinfunction "2_2") (pintype "passive"))
      (node (ref "C116") (pin "2") (pinfunction "2_2") (pintype "passive"))
      (node (ref "C117") (pin "2") (pinfunction "2_2") (pintype "passive"))
      (node (ref "C118") (pin "2") (pinfunction "2_2") (pintype "passive"))
      (node (ref "C119") (pin "2") (pinfunction "2_2") (pintype "passive"))
      (node (ref "C121") (pin "2") (pinfunction "2_2") (pintype "passive"))
      (node (ref "C122") (pin "2") (pinfunction "2_2") (pintype "passive"))
      (node (ref "C83") (pin "2") (pinfunction "2_2") (pintype "passive"))
      (node (ref "C84") (pin "2") (pinfunction "2_2") (pintype "passive"))
      (node (ref "C85") (pin "2") (pinfunction "2_2") (pintype "passive"))
      (node (ref "C86") (pin "2") (pinfunction "2_2") (pintype "passive"))
      (node (ref "C87") (pin "2") (pinfunction "2_2") (pintype "passive"))
      (node (ref "C88") (pin "2") (pinfunction "2_2") (pintype "passive"))
      (node (ref "C89") (pin "2") (pinfunction "2_2") (pintype "passive"))
      (node (ref "C90") (pin "2") (pinfunction "2_2") (pintype "passive"))
      (node (ref "C91") (pin "2") (pinfunction "2_2") (pintype "passive"))
      (node (ref "C92") (pin "2") (pinfunction "2_2") (pintype "passive"))
      (node (ref "C93") (pin "2") (pinfunction "2_2") (pintype "passive"))
      (node (ref "C94") (pin "2") (pinfunction "2_2") (pintype "passive"))
      (node (ref "C95") (pin "2") (pinfunction "2_2") (pintype "passive"))
      (node (ref "C96") (pin "2") (pinfunction "2_2") (pintype "passive"))
      (node (ref "C97") (pin "2") (pinfunction "2_2") (pintype "passive"))
      (node (ref "C98") (pin "2") (pinfunction "2_2") (pintype "passive"))
      (node (ref "D10") (pin "10") (pinfunction "VIN_10") (pintype "power_in"))
      (node (ref "D10") (pin "2") (pinfunction "VLDOIN_2") (pintype "power_in"))
      (node (ref "D10") (pin "7") (pinfunction "EN_7") (pintype "input"))
      (node (ref "D8") (pin "A1") (pinfunction "VDDQ_A1") (pintype "power_in"))
      (node (ref "D8") (pin "A8") (pinfunction "VDDQ_A8") (pintype "power_in"))
      (node (ref "D8") (pin "B2") (pinfunction "VDD_B2") (pintype "power_in"))
      (node (ref "D8") (pin "C1") (pinfunction "VDDQ_C1") (pintype "power_in"))
      (node (ref "D8") (pin "C9") (pinfunction "VDDQ_C9") (pintype "power_in"))
      (node (ref "D8") (pin "D2") (pinfunction "VDDQ_D2") (pintype "power_in"))
      (node (ref "D8") (pin "D9") (pinfunction "VDD_D9") (pintype "power_in"))
      (node (ref "D8") (pin "E9") (pinfunction "VDDQ_E9") (pintype "power_in"))
      (node (ref "D8") (pin "F1") (pinfunction "VDDQ_F1") (pintype "power_in"))
      (node (ref "D8") (pin "G7") (pinfunction "VDD_G7") (pintype "power_in"))
      (node (ref "D8") (pin "H2") (pinfunction "VDDQ_H2") (pintype "power_in"))
      (node (ref "D8") (pin "H9") (pinfunction "VDDQ_H9") (pintype "power_in"))
      (node (ref "D8") (pin "K2") (pinfunction "VDD_K2") (pintype "power_in"))
      (node (ref "D8") (pin "K8") (pinfunction "VDD_K8") (pintype "power_in"))
      (node (ref "D8") (pin "N1") (pinfunction "VDD_N1") (pintype "power_in"))
      (node (ref "D8") (pin "N9") (pinfunction "VDD_N9") (pintype "power_in"))
      (node (ref "D8") (pin "R1") (pinfunction "VDD_R1") (pintype "power_in"))
      (node (ref "D8") (pin "R9") (pinfunction "VDD_R9") (pintype "power_in"))
      (node (ref "D9") (pin "A1") (pinfunction "VDDQ_A1") (pintype "power_in"))
      (node (ref "D9") (pin "A8") (pinfunction "VDDQ_A8") (pintype "power_in"))
      (node (ref "D9") (pin "B2") (pinfunction "VDD_B2") (pintype "power_in"))
      (node (ref "D9") (pin "C1") (pinfunction "VDDQ_C1") (pintype "power_in"))
      (node (ref "D9") (pin "C9") (pinfunction "VDDQ_C9") (pintype "power_in"))
      (node (ref "D9") (pin "D2") (pinfunction "VDDQ_D2") (pintype "power_in"))
      (node (ref "D9") (pin "D9") (pinfunction "VDD_D9") (pintype "power_in"))
      (node (ref "D9") (pin "E9") (pinfunction "VDDQ_E9") (pintype "power_in"))
      (node (ref "D9") (pin "F1") (pinfunction "VDDQ_F1") (pintype "power_in"))
      (node (ref "D9") (pin "G7") (pinfunction "VDD_G7") (pintype "power_in"))
      (node (ref "D9") (pin "H2") (pinfunction "VDDQ_H2") (pintype "power_in"))
      (node (ref "D9") (pin "H9") (pinfunction "VDDQ_H9") (pintype "power_in"))
      (node (ref "D9") (pin "K2") (pinfunction "VDD_K2") (pintype "power_in"))
      (node (ref "D9") (pin "K8") (pinfunction "VDD_K8") (pintype "power_in"))
      (node (ref "D9") (pin "N1") (pinfunction "VDD_N1") (pintype "power_in"))
      (node (ref "D9") (pin "N9") (pinfunction "VDD_N9") (pintype "power_in"))
      (node (ref "D9") (pin "R1") (pinfunction "VDD_R1") (pintype "power_in"))
      (node (ref "D9") (pin "R9") (pinfunction "VDD_R9") (pintype "power_in"))
      (node (ref "R66") (pin "1") (pinfunction "1_1") (pintype "passive"))
      (node (ref "R67") (pin "2") (pinfunction "2_2") (pintype "passive"))
    )
    (net (code "75") (name "/vRefDDR") (class "Default")
      (node (ref "C79") (pin "2") (pinfunction "2_2") (pintype "passive"))
      (node (ref "C80") (pin "2") (pinfunction "2_2") (pintype "passive"))
      (node (ref "C81") (pin "2") (pinfunction "2_2") (pintype "passive"))
      (node (ref "C82") (pin "2") (pinfunction "2_2") (pintype "passive"))
      (node (ref "D8") (pin "H1") (pinfunction "VREFDQ_H1") (pintype "input"))
      (node (ref "D8") (pin "M8") (pinfunction "VREFCA_M8") (pintype "input"))
      (node (ref "D9") (pin "H1") (pinfunction "VREFDQ_H1") (pintype "input"))
      (node (ref "D9") (pin "M8") (pinfunction "VREFCA_M8") (pintype "input"))
      (node (ref "L9") (pin "2") (pinfunction "2_2") (pintype "passive"))
    )
    (net (code "76") (name "Net-(C78-Pad2)") (class "Default")
      (node (ref "C78") (pin "2") (pinfunction "2_2") (pintype "passive"))
      (node (ref "R63") (pin "2") (pinfunction "2_2") (pintype "passive"))
      (node (ref "R64") (pin "1") (pinfunction "1_1") (pintype "passive"))
    )
    (net (code "77") (name "Net-(D8A-ZQ)") (class "Default")
      (node (ref "D8") (pin "L8") (pinfunction "ZQ_L8") (pintype "input"))
      (node (ref "R61") (pin "1") (pinfunction "1_1") (pintype "passive"))
    )
    (net (code "78") (name "Net-(D9A-ZQ)") (class "Default")
      (node (ref "D9") (pin "L8") (pinfunction "ZQ_L8") (pintype "input"))
      (node (ref "R62") (pin "1") (pinfunction "1_1") (pintype "passive"))
    )
    (net (code "79") (name "Net-(D10-REFIN)") (class "Default")
      (node (ref "C120") (pin "2") (pinfunction "2_2") (pintype "passive"))
      (node (ref "D10") (pin "1") (pinfunction "REFIN_1") (pintype "input"))
      (node (ref "R67") (pin "1") (pinfunction "1_1") (pintype "passive"))
      (node (ref "R68") (pin "2") (pinfunction "2_2") (pintype "passive"))
    )
    (net (code "80") (name "Net-(D10-REFOUT)") (class "Default")
      (node (ref "C103") (pin "2") (pinfunction "2_2") (pintype "passive"))
      (node (ref "D10") (pin "6") (pinfunction "REFOUT_6") (pintype "output"))
    )
    (net (code "81") (name "Net-(R55B-1)") (class "Default")
      (node (ref "C70") (pin "1") (pinfunction "1_1") (pintype "passive"))
      (node (ref "C71") (pin "1") (pinfunction "1_1") (pintype "passive"))
      (node (ref "C72") (pin "1") (pinfunction "1_1") (pintype "passive"))
      (node (ref "C73") (pin "1") (pinfunction "1_1") (pintype "passive"))
      (node (ref "C74") (pin "1") (pinfunction "1_1") (pintype "passive"))
      (node (ref "C75") (pin "1") (pinfunction "1_1") (pintype "passive"))
      (node (ref "C76") (pin "2") (pinfunction "2_2") (pintype "passive"))
      (node (ref "C77") (pin "2") (pinfunction "2_2") (pintype "passive"))
      (node (ref "L8") (pin "1") (pinfunction "1_1") (pintype "passive"))
      (node (ref "R55") (pin "1") (pinfunction "1_1") (pintype "passive"))
      (node (ref "R55") (pin "2") (pinfunction "1_2") (pintype "passive"))
      (node (ref "R55") (pin "3") (pinfunction "1_3") (pintype "passive"))
      (node (ref "R55") (pin "4") (pinfunction "1_4") (pintype "passive"))
      (node (ref "R56") (pin "1") (pinfunction "1_1") (pintype "passive"))
      (node (ref "R56") (pin "2") (pinfunction "1_2") (pintype "passive"))
      (node (ref "R56") (pin "3") (pinfunction "1_3") (pintype "passive"))
      (node (ref "R56") (pin "4") (pinfunction "1_4") (pintype "passive"))
      (node (ref "R57") (pin "1") (pinfunction "1_1") (pintype "passive"))
      (node (ref "R57") (pin "2") (pinfunction "1_2") (pintype "passive"))
      (node (ref "R57") (pin "3") (pinfunction "1_3") (pintype "passive"))
      (node (ref "R57") (pin "4") (pinfunction "1_4") (pintype "passive"))
      (node (ref "R58") (pin "1") (pinfunction "1_1") (pintype "passive"))
      (node (ref "R58") (pin "2") (pinfunction "1_2") (pintype "passive"))
      (node (ref "R58") (pin "3") (pinfunction "1_3") (pintype "passive"))
      (node (ref "R58") (pin "4") (pinfunction "1_4") (pintype "passive"))
      (node (ref "R59") (pin "1") (pinfunction "1_1") (pintype "passive"))
      (node (ref "R59") (pin "2") (pinfunction "1_2") (pintype "passive"))
      (node (ref "R59") (pin "3") (pinfunction "1_3") (pintype "passive"))
      (node (ref "R59") (pin "4") (pinfunction "1_4") (pintype "passive"))
      (node (ref "R60") (pin "1") (pinfunction "1_1") (pintype "passive"))
      (node (ref "R60") (pin "2") (pinfunction "1_2") (pintype "passive"))
      (node (ref "R60") (pin "3") (pinfunction "1_3") (pintype "passive"))
      (node (ref "R60") (pin "4") (pinfunction "1_4") (pintype "passive"))
    )
    (net (code "82") (name "unconnected-(D8C-NC-PadJ1)") (class "Default")
      (node (ref "D8") (pin "J1") (pinfunction "NC_J1") (pintype "passive"))
    )
    (net (code "83") (name "unconnected-(D8C-NC-PadJ9)") (class "Default")
      (node (ref "D8") (pin "J9") (pinfunction "NC_J9") (pintype "passive"))
    )
    (net (code "84") (name "unconnected-(D8C-NC-PadL1)") (class "Default")
      (node (ref "D8") (pin "L1") (pinfunction "NC_L1") (pintype "passive"))
    )
    (net (code "85") (name "unconnected-(D8C-NC-PadL9)") (class "Default")
      (node (ref "D8") (pin "L9") (pinfunction "NC_L9") (pintype "passive"))
    )
    (net (code "86") (name "unconnected-(D8C-NC-PadM7)") (class "Default")
      (node (ref "D8") (pin "M7") (pinfunction "NC_M7") (pintype "passive"))
    )
    (net (code "87") (name "unconnected-(D9C-NC-PadJ1)") (class "Default")
      (node (ref "D9") (pin "J1") (pinfunction "NC_J1") (pintype "passive"))
    )
    (net (code "88") (name "unconnected-(D9C-NC-PadJ9)") (class "Default")
      (node (ref "D9") (pin "J9") (pinfunction "NC_J9") (pintype "passive"))
    )
    (net (code "89") (name "unconnected-(D9C-NC-PadL1)") (class "Default")
      (node (ref "D9") (pin "L1") (pinfunction "NC_L1") (pintype "passive"))
    )
    (net (code "90") (name "unconnected-(D9C-NC-PadL9)") (class "Default")
      (node (ref "D9") (pin "L9") (pinfunction "NC_L9") (pintype "passive"))
    )
    (net (code "91") (name "unconnected-(D9C-NC-PadM7)") (class "Default")
      (node (ref "D9") (pin "M7") (pinfunction "NC_M7") (pintype "passive"))
    )
    (net (code "92") (name "unconnected-(D10-PGOOD-Pad9)") (class "Default")
      (node (ref "D10") (pin "9") (pinfunction "PGOOD_9") (pintype "open_collector"))
    )
    (net (code "93") (name "unconnected-(R55A-2-Pad8)") (class "Default")
      (node (ref "R55") (pin "8") (pinfunction "2_8") (pintype "passive"))
    )
    (net (code "94") (name "unconnected-(R55B-2-Pad7)") (class "Default")
      (node (ref "R55") (pin "7") (pinfunction "2_7") (pintype "passive"))
    )
    (net (code "95") (name "unconnected-(R55C-2-Pad6)") (class "Default")
      (node (ref "R55") (pin "6") (pinfunction "2_6") (pintype "passive"))
    )
    (net (code "96") (name "unconnected-(R55D-2-Pad5)") (class "Default")
      (node (ref "R55") (pin "5") (pinfunction "2_5") (pintype "passive"))
    )
    (net (code "97") (name "unconnected-(R56C-2-Pad8)") (class "Default")
      (node (ref "R56") (pin "8") (pinfunction "2_8") (pintype "passive"))
    )
    (net (code "98") (name "unconnected-(R60A-2-Pad8)") (class "Default")
      (node (ref "R60") (pin "8") (pinfunction "2_8") (pintype "passive"))
    )
    (net (code "99") (name "unconnected-(R60B-2-Pad6)") (class "Default")
      (node (ref "R60") (pin "6") (pinfunction "2_6") (pintype "passive"))
    )
    (net (code "100") (name "unconnected-(R60C-2-Pad7)") (class "Default")
      (node (ref "R60") (pin "7") (pinfunction "2_7") (pintype "passive"))
    )
    (net (code "101") (name "unconnected-(R60D-2-Pad5)") (class "Default")
      (node (ref "R60") (pin "5") (pinfunction "2_5") (pintype "passive"))
    )
  )
)
